# M_D_ext_power_usb_centered_M9.net
KiCad netlist of a schematic drawn in EAGLE
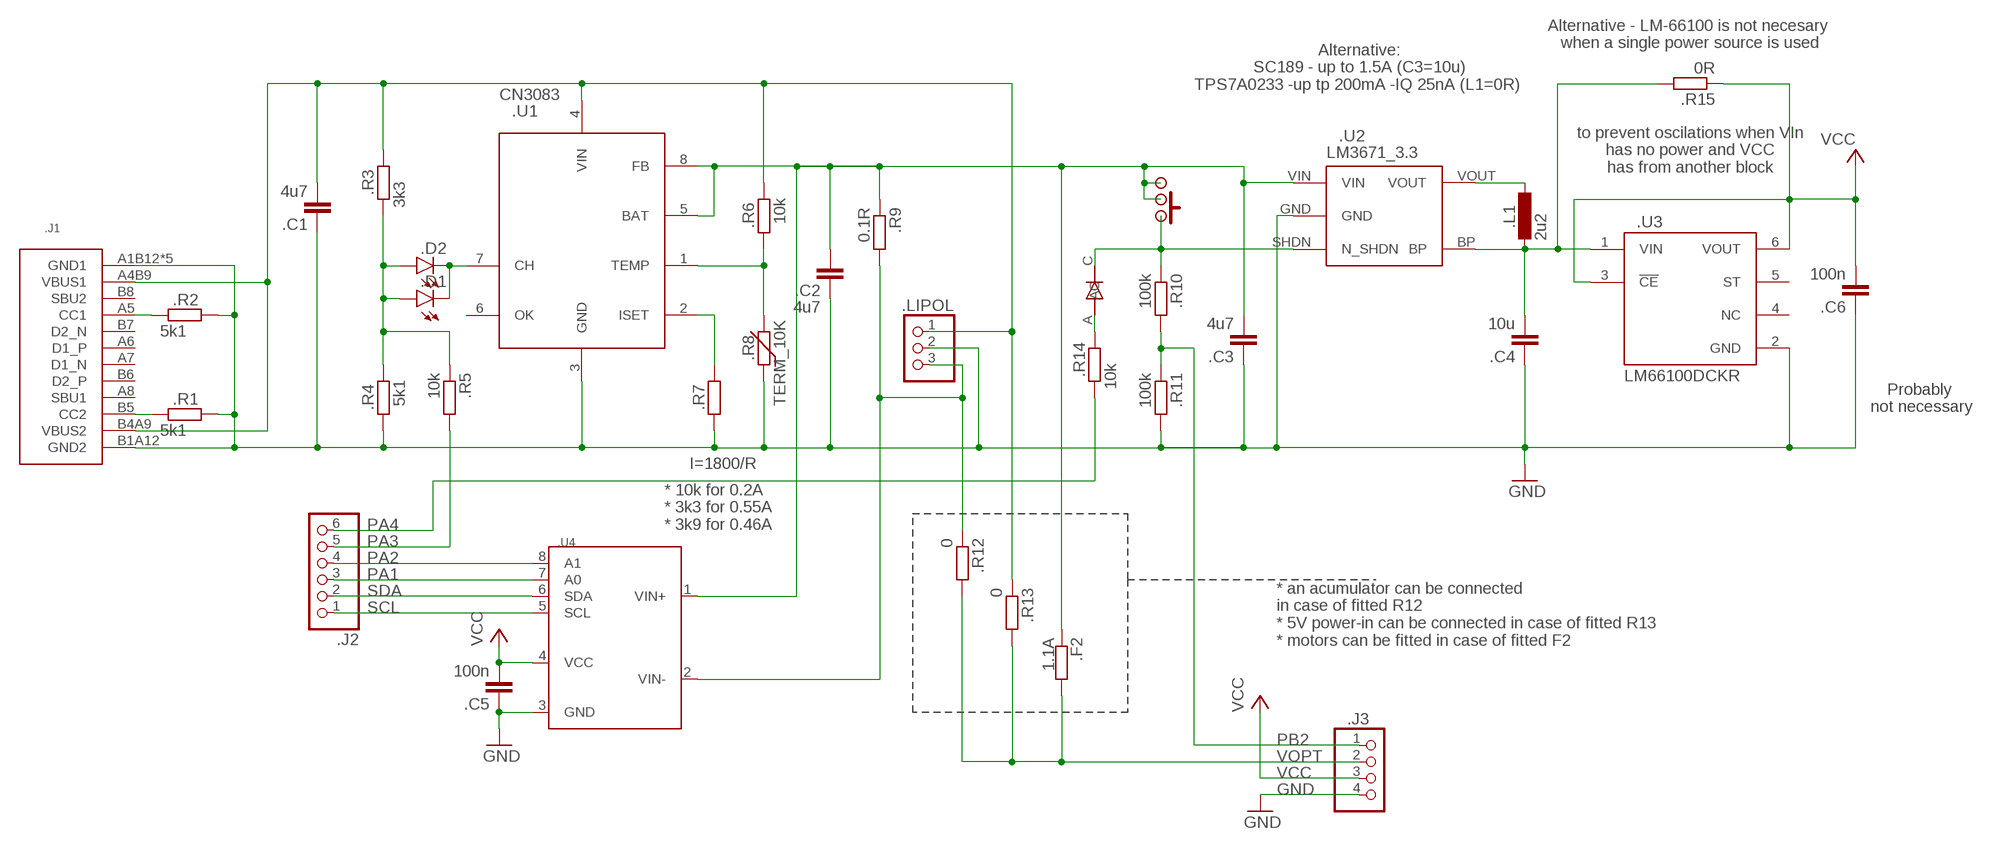
[diagram p0: schematic, sheet 1]

(export (version "E")
  (design (tool "Eeschema 10.0.6"))
  (components
    (comp (ref "Ḋ.BTN")
      (value "SWITCH")
      (footprint "eagle-import:SWITCH")
      (libsource (lib "eagle-import") (part "SWITCH"))
    )
    (comp (ref "Ḋ.C1")
      (value "4u7")
      (footprint "eagle-import:C0603")
      (libsource (lib "eagle-import") (part "C-EUC0603"))
    )
    (comp (ref "Ḋ.C2")
      (value "4u7")
      (footprint "eagle-import:C0603")
      (libsource (lib "eagle-import") (part "C-EUC0603"))
    )
    (comp (ref "Ḋ.C3")
      (value "4u7")
      (footprint "eagle-import:C0603")
      (libsource (lib "eagle-import") (part "C-EUC0603"))
    )
    (comp (ref "Ḋ.C4")
      (value "10u")
      (footprint "eagle-import:C0603")
      (libsource (lib "eagle-import") (part "C-EUC0603"))
    )
    (comp (ref "Ḋ.C5")
      (value "100n")
      (footprint "eagle-import:C0603")
      (libsource (lib "eagle-import") (part "C-EUC0603"))
    )
    (comp (ref "Ḋ.C6")
      (value "100n")
      (footprint "eagle-import:C0603")
      (libsource (lib "eagle-import") (part "C-EUC0603"))
    )
    (comp (ref "Ḋ.D1")
      (value "LEDCHIP-LED0603")
      (footprint "eagle-import:CHIP-LED0603")
      (libsource (lib "eagle-import") (part "LEDCHIP-LED0603"))
    )
    (comp (ref "Ḋ.D2")
      (value "LEDCHIP-LED0603")
      (footprint "eagle-import:CHIP-LED0603")
      (libsource (lib "eagle-import") (part "LEDCHIP-LED0603"))
    )
    (comp (ref "Ḋ.D3")
      (value "DIODE")
      (footprint "eagle-import:DIODE")
      (libsource (lib "eagle-import") (part "DIODE"))
    )
    (comp (ref "Ḋ.F2")
      (value "1.1A")
      (footprint "eagle-import:R0805")
      (libsource (lib "eagle-import") (part "R-EU_R0805"))
    )
    (comp (ref "Ḋ.J1")
      (value "USB-C")
      (footprint "eagle-import:USB-C")
      (libsource (lib "eagle-import") (part "USB-C"))
    )
    (comp (ref "Ḋ.J2")
      (value "PINHD-1X6")
      (footprint "eagle-import:1X06")
      (libsource (lib "eagle-import") (part "PINHD-1X6"))
    )
    (comp (ref "Ḋ.J3")
      (value "PINHD-1X4")
      (footprint "eagle-import:1X04")
      (libsource (lib "eagle-import") (part "PINHD-1X4"))
    )
    (comp (ref "Ḋ.L1")
      (value "2u2")
      (footprint "eagle-import:L3230M")
      (libsource (lib "eagle-import") (part "L-EUL3230M"))
    )
    (comp (ref "Ḋ.LIPOL")
      (value "PINHEAD-1X3-2")
      (footprint "eagle-import:1X-03-2")
      (libsource (lib "eagle-import") (part "PINHEAD-1X3-2"))
    )
    (comp (ref "Ḋ.R1")
      (value "5k1")
      (footprint "eagle-import:R0603")
      (libsource (lib "eagle-import") (part "R-EU_R0603"))
    )
    (comp (ref "Ḋ.R2")
      (value "5k1")
      (footprint "eagle-import:R0603")
      (libsource (lib "eagle-import") (part "R-EU_R0603"))
    )
    (comp (ref "Ḋ.R3")
      (value "3k3")
      (footprint "eagle-import:R0603")
      (libsource (lib "eagle-import") (part "R-EU_R0603"))
    )
    (comp (ref "Ḋ.R4")
      (value "5k1")
      (footprint "eagle-import:R0603")
      (libsource (lib "eagle-import") (part "R-EU_R0603"))
    )
    (comp (ref "Ḋ.R5")
      (value "10k")
      (footprint "eagle-import:R0603")
      (libsource (lib "eagle-import") (part "R-EU_R0603"))
    )
    (comp (ref "Ḋ.R6")
      (value "10k")
      (footprint "eagle-import:R0603")
      (libsource (lib "eagle-import") (part "R-EU_R0603"))
    )
    (comp (ref "Ḋ.R7")
      (value "I=1800/R")
      (footprint "eagle-import:R0603")
      (libsource (lib "eagle-import") (part "R-EU_R0603"))
    )
    (comp (ref "Ḋ.R8")
      (value "TERM_10K")
      (footprint "eagle-import:THERM")
      (libsource (lib "eagle-import") (part "THERM"))
    )
    (comp (ref "Ḋ.R9")
      (value "0.1R")
      (footprint "eagle-import:R0805")
      (libsource (lib "eagle-import") (part "R-EU_R0805"))
    )
    (comp (ref "Ḋ.R10")
      (value "100k")
      (footprint "eagle-import:R0603")
      (libsource (lib "eagle-import") (part "R-EU_R0603"))
    )
    (comp (ref "Ḋ.R11")
      (value "100k")
      (footprint "eagle-import:R0603")
      (libsource (lib "eagle-import") (part "R-EU_R0603"))
    )
    (comp (ref "Ḋ.R12")
      (value "0")
      (footprint "eagle-import:R0603")
      (libsource (lib "eagle-import") (part "R-EU_R0603"))
    )
    (comp (ref "Ḋ.R13")
      (value "0")
      (footprint "eagle-import:R0603")
      (libsource (lib "eagle-import") (part "R-EU_R0603"))
    )
    (comp (ref "Ḋ.R14")
      (value "10k")
      (footprint "eagle-import:R0603")
      (libsource (lib "eagle-import") (part "R-EU_R0603"))
    )
    (comp (ref "Ḋ.R15")
      (value "0R")
      (footprint "eagle-import:R0603")
      (libsource (lib "eagle-import") (part "R-EU_R0603"))
    )
    (comp (ref "Ḋ.U1")
      (value "CN3083")
      (footprint "eagle-import:SOP8")
      (libsource (lib "eagle-import") (part "CN3083"))
    )
    (comp (ref "Ḋ.U2")
      (value "LM3671_3.3")
      (footprint "eagle-import:SOT32-5")
      (libsource (lib "eagle-import") (part "STABILISER_APE8865"))
    )
    (comp (ref "Ḋ.U3")
      (value "LM66100DCKR")
      (footprint "eagle-import:SOT65P210X110-6N")
      (fields (field (name "MF") "Texas Instruments"))
      (libsource (lib "eagle-import") (part "LM66100DCKR"))
    )
    (comp (ref "Ḋ.U4")
      (value "INA219")
      (footprint "eagle-import:SOT23-8")
      (libsource (lib "eagle-import") (part "INA219"))
    )
  )
  (nets
    (net (code "1") (name "/PA1") (class "Default")
      (node (ref "Ḋ.J2") (pin "3") (pinfunction "3_3") (pintype "passive"))
      (node (ref "Ḋ.U4") (pin "7") (pinfunction "A0_7") (pintype "bidirectional"))
    )
    (net (code "2") (name "/PA2") (class "Default")
      (node (ref "Ḋ.J2") (pin "4") (pinfunction "4_4") (pintype "passive"))
      (node (ref "Ḋ.U4") (pin "8") (pinfunction "A1_8") (pintype "bidirectional"))
    )
    (net (code "3") (name "/PA3") (class "Default")
      (node (ref "Ḋ.J2") (pin "5") (pinfunction "5_5") (pintype "passive"))
      (node (ref "Ḋ.R5") (pin "2") (pinfunction "2_2") (pintype "passive"))
    )
    (net (code "4") (name "/PA4") (class "Default")
      (node (ref "Ḋ.J2") (pin "6") (pinfunction "6_6") (pintype "passive"))
      (node (ref "Ḋ.R14") (pin "1") (pinfunction "1_1") (pintype "passive"))
    )
    (net (code "5") (name "/PB2") (class "Default")
      (node (ref "Ḋ.J3") (pin "1") (pinfunction "1_1") (pintype "passive"))
      (node (ref "Ḋ.R10") (pin "2") (pinfunction "2_2") (pintype "passive"))
      (node (ref "Ḋ.R11") (pin "1") (pinfunction "1_1") (pintype "passive"))
    )
    (net (code "6") (name "/SCL") (class "Default")
      (node (ref "Ḋ.J2") (pin "1") (pinfunction "1_1") (pintype "passive"))
      (node (ref "Ḋ.U4") (pin "5") (pinfunction "SCL_5") (pintype "bidirectional"))
    )
    (net (code "7") (name "/SDA") (class "Default")
      (node (ref "Ḋ.J2") (pin "2") (pinfunction "2_2") (pintype "passive"))
      (node (ref "Ḋ.U4") (pin "6") (pinfunction "SDA_6") (pintype "bidirectional"))
    )
    (net (code "8") (name "/VOPT") (class "Default")
      (node (ref "Ḋ.F2") (pin "2") (pinfunction "2_2") (pintype "passive"))
      (node (ref "Ḋ.J3") (pin "2") (pinfunction "2_2") (pintype "passive"))
      (node (ref "Ḋ.R12") (pin "2") (pinfunction "2_2") (pintype "passive"))
      (node (ref "Ḋ.R13") (pin "2") (pinfunction "2_2") (pintype "passive"))
    )
    (net (code "9") (name "GND") (class "Default")
      (node (ref "Ḋ.C1") (pin "1") (pinfunction "1_1") (pintype "passive"))
      (node (ref "Ḋ.C2") (pin "1") (pinfunction "1_1") (pintype "passive"))
      (node (ref "Ḋ.C3") (pin "1") (pinfunction "1_1") (pintype "passive"))
      (node (ref "Ḋ.C4") (pin "1") (pinfunction "1_1") (pintype "passive"))
      (node (ref "Ḋ.C5") (pin "1") (pinfunction "1_1") (pintype "passive"))
      (node (ref "Ḋ.C6") (pin "1") (pinfunction "1_1") (pintype "passive"))
      (node (ref "Ḋ.J1") (pin "A1B12") (pinfunction "GND1_A1B12") (pintype "bidirectional"))
      (node (ref "Ḋ.J1") (pin "B1A12") (pinfunction "GND2_B1A12") (pintype "bidirectional"))
      (node (ref "Ḋ.J1") (pin "SH1") (pinfunction "GND1_SH1") (pintype "bidirectional"))
      (node (ref "Ḋ.J1") (pin "SH2") (pinfunction "GND1_SH2") (pintype "bidirectional"))
      (node (ref "Ḋ.J1") (pin "SH3") (pinfunction "GND1_SH3") (pintype "bidirectional"))
      (node (ref "Ḋ.J1") (pin "SH4") (pinfunction "GND1_SH4") (pintype "bidirectional"))
      (node (ref "Ḋ.J3") (pin "4") (pinfunction "4_4") (pintype "passive"))
      (node (ref "Ḋ.LIPOL") (pin "2") (pinfunction "2_2") (pintype "passive"))
      (node (ref "Ḋ.R1") (pin "2") (pinfunction "2_2") (pintype "passive"))
      (node (ref "Ḋ.R11") (pin "2") (pinfunction "2_2") (pintype "passive"))
      (node (ref "Ḋ.R2") (pin "2") (pinfunction "2_2") (pintype "passive"))
      (node (ref "Ḋ.R4") (pin "1") (pinfunction "1_1") (pintype "passive"))
      (node (ref "Ḋ.R7") (pin "1") (pinfunction "1_1") (pintype "passive"))
      (node (ref "Ḋ.R8") (pin "1") (pinfunction "1_1") (pintype "passive"))
      (node (ref "Ḋ.U1") (pin "3") (pinfunction "GND_3") (pintype "bidirectional"))
      (node (ref "Ḋ.U2") (pin "GND") (pinfunction "GND_GND") (pintype "bidirectional"))
      (node (ref "Ḋ.U3") (pin "2") (pinfunction "GND_2") (pintype "power_in"))
      (node (ref "Ḋ.U4") (pin "3") (pinfunction "GND_3") (pintype "bidirectional"))
    )
    (net (code "10") (name "Net-(Ḋ.D1-A)") (class "Default")
      (node (ref "Ḋ.D1") (pin "A1") (pinfunction "A_A1") (pintype "passive"))
      (node (ref "Ḋ.D2") (pin "A1") (pinfunction "A_A1") (pintype "passive"))
      (node (ref "Ḋ.R3") (pin "1") (pinfunction "1_1") (pintype "passive"))
      (node (ref "Ḋ.R4") (pin "2") (pinfunction "2_2") (pintype "passive"))
      (node (ref "Ḋ.R5") (pin "1") (pinfunction "1_1") (pintype "passive"))
    )
    (net (code "11") (name "Net-(Ḋ.D1-C)") (class "Default")
      (node (ref "Ḋ.D1") (pin "C1") (pinfunction "C_C1") (pintype "passive"))
      (node (ref "Ḋ.D2") (pin "C1") (pinfunction "C_C1") (pintype "passive"))
      (node (ref "Ḋ.U1") (pin "7") (pinfunction "CH_7") (pintype "bidirectional"))
    )
    (net (code "12") (name "Net-(Ḋ.D3-PadA)") (class "Default")
      (node (ref "Ḋ.D3") (pin "A") (pinfunction "A_A") (pintype "bidirectional"))
      (node (ref "Ḋ.R14") (pin "2") (pinfunction "2_2") (pintype "passive"))
    )
    (net (code "13") (name "Net-(Ḋ.J1-CC1)") (class "Default")
      (node (ref "Ḋ.J1") (pin "A5") (pinfunction "CC1_A5") (pintype "bidirectional"))
      (node (ref "Ḋ.R2") (pin "1") (pinfunction "1_1") (pintype "passive"))
    )
    (net (code "14") (name "Net-(Ḋ.J1-CC2)") (class "Default")
      (node (ref "Ḋ.J1") (pin "B5") (pinfunction "CC2_B5") (pintype "bidirectional"))
      (node (ref "Ḋ.R1") (pin "1") (pinfunction "1_1") (pintype "passive"))
    )
    (net (code "15") (name "Net-(Ḋ.J1-VBUS1)") (class "Default")
      (node (ref "Ḋ.C1") (pin "2") (pinfunction "2_2") (pintype "passive"))
      (node (ref "Ḋ.J1") (pin "A4B9") (pinfunction "VBUS1_A4B9") (pintype "bidirectional"))
      (node (ref "Ḋ.J1") (pin "B4A9") (pinfunction "VBUS2_B4A9") (pintype "bidirectional"))
      (node (ref "Ḋ.LIPOL") (pin "1") (pinfunction "1_1") (pintype "passive"))
      (node (ref "Ḋ.R13") (pin "1") (pinfunction "1_1") (pintype "passive"))
      (node (ref "Ḋ.R3") (pin "2") (pinfunction "2_2") (pintype "passive"))
      (node (ref "Ḋ.R6") (pin "2") (pinfunction "2_2") (pintype "passive"))
      (node (ref "Ḋ.U1") (pin "4") (pinfunction "VIN_4") (pintype "bidirectional"))
    )
    (net (code "16") (name "Net-(Ḋ.L1-Pad1)") (class "Default")
      (node (ref "Ḋ.L1") (pin "1") (pinfunction "1_1") (pintype "passive"))
      (node (ref "Ḋ.U2") (pin "VOUT") (pinfunction "VOUT_VOUT") (pintype "bidirectional"))
    )
    (net (code "17") (name "Net-(Ḋ.U1-BAT)") (class "Default")
      (node (ref "Ḋ.BTN") (pin "P$2") (pinfunction "P$2_P$2") (pintype "bidirectional"))
      (node (ref "Ḋ.BTN") (pin "P$3") (pinfunction "P$3_P$3") (pintype "bidirectional"))
      (node (ref "Ḋ.BTN") (pin "P$4") (pinfunction "P$3_P$4") (pintype "bidirectional"))
      (node (ref "Ḋ.BTN") (pin "P$6") (pinfunction "P$3_P$6") (pintype "bidirectional"))
      (node (ref "Ḋ.C2") (pin "2") (pinfunction "2_2") (pintype "passive"))
      (node (ref "Ḋ.C3") (pin "2") (pinfunction "2_2") (pintype "passive"))
      (node (ref "Ḋ.F2") (pin "1") (pinfunction "1_1") (pintype "passive"))
      (node (ref "Ḋ.R9") (pin "1") (pinfunction "1_1") (pintype "passive"))
      (node (ref "Ḋ.U1") (pin "5") (pinfunction "BAT_5") (pintype "bidirectional"))
      (node (ref "Ḋ.U1") (pin "8") (pinfunction "FB_8") (pintype "bidirectional"))
      (node (ref "Ḋ.U2") (pin "VIN") (pinfunction "VIN_VIN") (pintype "bidirectional"))
      (node (ref "Ḋ.U4") (pin "1") (pinfunction "VIN+_1") (pintype "bidirectional"))
    )
    (net (code "18") (name "Net-(Ḋ.U1-ISET)") (class "Default")
      (node (ref "Ḋ.R7") (pin "2") (pinfunction "2_2") (pintype "passive"))
      (node (ref "Ḋ.U1") (pin "2") (pinfunction "ISET_2") (pintype "bidirectional"))
    )
    (net (code "19") (name "Net-(Ḋ.U1-TEMP)") (class "Default")
      (node (ref "Ḋ.R6") (pin "1") (pinfunction "1_1") (pintype "passive"))
      (node (ref "Ḋ.R8") (pin "2") (pinfunction "2_2") (pintype "passive"))
      (node (ref "Ḋ.U1") (pin "1") (pinfunction "TEMP_1") (pintype "bidirectional"))
    )
    (net (code "20") (name "Net-(Ḋ.U2-N_SHDN)") (class "Default")
      (node (ref "Ḋ.BTN") (pin "P$1") (pinfunction "P$1_P$1") (pintype "bidirectional"))
      (node (ref "Ḋ.BTN") (pin "P$5") (pinfunction "P$1_P$5") (pintype "bidirectional"))
      (node (ref "Ḋ.BTN") (pin "P$7") (pinfunction "P$1_P$7") (pintype "bidirectional"))
      (node (ref "Ḋ.D3") (pin "C") (pinfunction "C_C") (pintype "bidirectional"))
      (node (ref "Ḋ.R10") (pin "1") (pinfunction "1_1") (pintype "passive"))
      (node (ref "Ḋ.U2") (pin "SHDN") (pinfunction "N_SHDN_SHDN") (pintype "bidirectional"))
    )
    (net (code "21") (name "Net-(Ḋ.U3-VIN)") (class "Default")
      (node (ref "Ḋ.C4") (pin "2") (pinfunction "2_2") (pintype "passive"))
      (node (ref "Ḋ.L1") (pin "2") (pinfunction "2_2") (pintype "passive"))
      (node (ref "Ḋ.R15") (pin "2") (pinfunction "2_2") (pintype "passive"))
      (node (ref "Ḋ.U2") (pin "BP") (pinfunction "BP_BP") (pintype "bidirectional"))
      (node (ref "Ḋ.U3") (pin "1") (pinfunction "VIN_1") (pintype "input"))
    )
    (net (code "22") (name "Net-(Ḋ.U4-VIN-)") (class "Default")
      (node (ref "Ḋ.LIPOL") (pin "3") (pinfunction "3_3") (pintype "passive"))
      (node (ref "Ḋ.R12") (pin "1") (pinfunction "1_1") (pintype "passive"))
      (node (ref "Ḋ.R9") (pin "2") (pinfunction "2_2") (pintype "passive"))
      (node (ref "Ḋ.U4") (pin "2") (pinfunction "VIN-_2") (pintype "bidirectional"))
    )
    (net (code "23") (name "VCC") (class "Default")
      (node (ref "Ḋ.C5") (pin "2") (pinfunction "2_2") (pintype "passive"))
      (node (ref "Ḋ.C6") (pin "2") (pinfunction "2_2") (pintype "passive"))
      (node (ref "Ḋ.J3") (pin "3") (pinfunction "3_3") (pintype "passive"))
      (node (ref "Ḋ.R15") (pin "1") (pinfunction "1_1") (pintype "passive"))
      (node (ref "Ḋ.U3") (pin "3") (pinfunction "~{CE}_3") (pintype "input"))
      (node (ref "Ḋ.U3") (pin "6") (pinfunction "VOUT_6") (pintype "output"))
      (node (ref "Ḋ.U4") (pin "4") (pinfunction "VCC_4") (pintype "bidirectional"))
    )
    (net (code "24") (name "unconnected-(Ḋ.J1-D1_N-PadA7)") (class "Default")
      (node (ref "Ḋ.J1") (pin "A7") (pinfunction "D1_N_A7") (pintype "bidirectional"))
    )
    (net (code "25") (name "unconnected-(Ḋ.J1-D1_P-PadA6)") (class "Default")
      (node (ref "Ḋ.J1") (pin "A6") (pinfunction "D1_P_A6") (pintype "bidirectional"))
    )
    (net (code "26") (name "unconnected-(Ḋ.J1-D2_N-PadB7)") (class "Default")
      (node (ref "Ḋ.J1") (pin "B7") (pinfunction "D2_N_B7") (pintype "bidirectional"))
    )
    (net (code "27") (name "unconnected-(Ḋ.J1-D2_P-PadB6)") (class "Default")
      (node (ref "Ḋ.J1") (pin "B6") (pinfunction "D2_P_B6") (pintype "bidirectional"))
    )
    (net (code "28") (name "unconnected-(Ḋ.J1-SBU1-PadA8)") (class "Default")
      (node (ref "Ḋ.J1") (pin "A8") (pinfunction "SBU1_A8") (pintype "bidirectional"))
    )
    (net (code "29") (name "unconnected-(Ḋ.J1-SBU2-PadB8)") (class "Default")
      (node (ref "Ḋ.J1") (pin "B8") (pinfunction "SBU2_B8") (pintype "bidirectional"))
    )
    (net (code "30") (name "unconnected-(Ḋ.U1-OK-Pad6)") (class "Default")
      (node (ref "Ḋ.U1") (pin "6") (pinfunction "OK_6") (pintype "bidirectional"))
    )
    (net (code "31") (name "unconnected-(Ḋ.U3-NC-Pad4)") (class "Default")
      (node (ref "Ḋ.U3") (pin "4") (pinfunction "NC_4") (pintype "no_connect"))
    )
    (net (code "32") (name "unconnected-(Ḋ.U3-ST-Pad5)") (class "Default")
      (node (ref "Ḋ.U3") (pin "5") (pinfunction "ST_5") (pintype "output"))
    )
  )
)
